# Adafruit_DRV8833.net
KiCad netlist of a schematic drawn in EAGLE
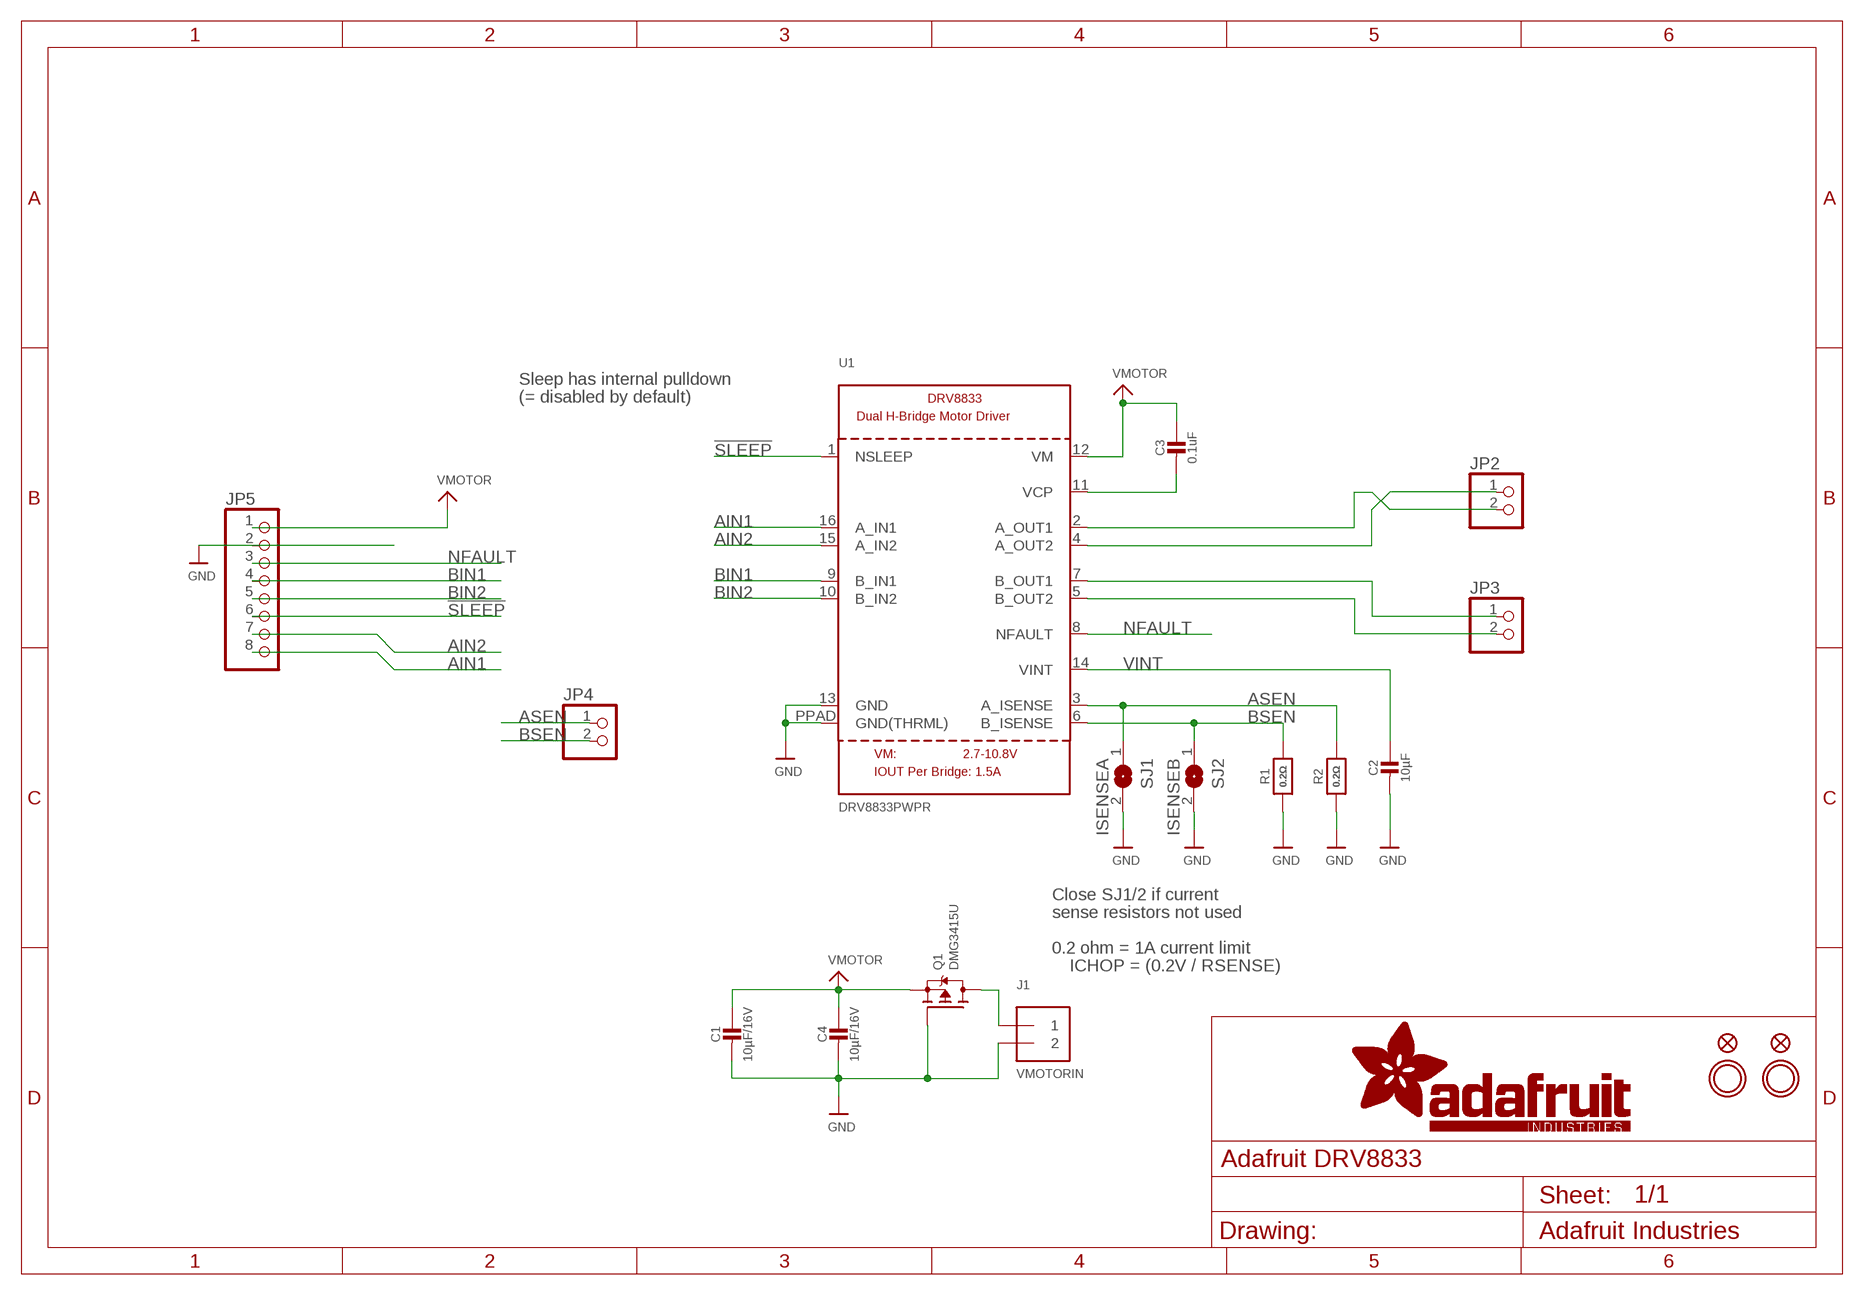
[diagram p0: schematic, sheet 1]

(export (version "E")
  (design (tool "Eeschema 10.0.6"))
  (components
    (comp (ref "C1")
      (value "10µF/16V")
      (footprint "eagle-import:0805-NO")
      (libsource (lib "eagle-import") (part "CAP_CERAMIC0805-NOOUTLINE"))
    )
    (comp (ref "C2")
      (value "10µF")
      (footprint "eagle-import:0805-NO")
      (libsource (lib "eagle-import") (part "CAP_CERAMIC0805-NOOUTLINE"))
    )
    (comp (ref "C3")
      (value "0.1uF")
      (footprint "eagle-import:0805-NO")
      (libsource (lib "eagle-import") (part "CAP_CERAMIC0805-NOOUTLINE"))
    )
    (comp (ref "C4")
      (value "10µF/16V")
      (footprint "eagle-import:0805-NO")
      (libsource (lib "eagle-import") (part "CAP_CERAMIC0805-NOOUTLINE"))
    )
    (comp (ref "FID1")
      (value "FIDUCIAL\"\"")
      (footprint "eagle-import:FIDUCIAL_1MM")
      (libsource (lib "eagle-import") (part "FIDUCIAL{dblquote}{dblquote}"))
    )
    (comp (ref "FID2")
      (value "FIDUCIAL\"\"")
      (footprint "eagle-import:FIDUCIAL_1MM")
      (libsource (lib "eagle-import") (part "FIDUCIAL{dblquote}{dblquote}"))
    )
    (comp (ref "J1")
      (value "VMOTORIN")
      (footprint "eagle-import:TERMBLOCK_1X2-3.5MM")
      (libsource (lib "eagle-import") (part "TERMBLOCK_1X2"))
    )
    (comp (ref "JP2")
      (value "HEADER-1X2ROUND")
      (footprint "eagle-import:1X02_ROUND")
      (libsource (lib "eagle-import") (part "HEADER-1X2ROUND"))
    )
    (comp (ref "JP3")
      (value "HEADER-1X2ROUND")
      (footprint "eagle-import:1X02_ROUND")
      (libsource (lib "eagle-import") (part "HEADER-1X2ROUND"))
    )
    (comp (ref "JP4")
      (value "HEADER-1X2ROUND")
      (footprint "eagle-import:1X02_ROUND")
      (libsource (lib "eagle-import") (part "HEADER-1X2ROUND"))
    )
    (comp (ref "JP5")
      (value "HEADER-1X870MIL")
      (footprint "eagle-import:1X08_ROUND_70")
      (libsource (lib "eagle-import") (part "HEADER-1X870MIL"))
    )
    (comp (ref "Q1")
      (value "DMG3415U")
      (footprint "eagle-import:SOT23-WIDE")
      (libsource (lib "eagle-import") (part "MOSFET-PWIDE"))
    )
    (comp (ref "R1")
      (value "0.2Ω")
      (footprint "eagle-import:_1206")
      (libsource (lib "eagle-import") (part "RESISTOR_1206"))
    )
    (comp (ref "R2")
      (value "0.2Ω")
      (footprint "eagle-import:_1206")
      (libsource (lib "eagle-import") (part "RESISTOR_1206"))
    )
    (comp (ref "SJ1")
      (value "ISENSEA")
      (footprint "eagle-import:SOLDERJUMPER_ARROW_NOPASTE")
      (libsource (lib "eagle-import") (part "SOLDERJUMPER"))
    )
    (comp (ref "SJ2")
      (value "ISENSEB")
      (footprint "eagle-import:SOLDERJUMPER_ARROW_NOPASTE")
      (libsource (lib "eagle-import") (part "SOLDERJUMPER"))
    )
    (comp (ref "U$13")
      (value "MOUNTINGHOLE2.5")
      (footprint "eagle-import:MOUNTINGHOLE_2.5_PLATED")
      (libsource (lib "eagle-import") (part "MOUNTINGHOLE2.5"))
    )
    (comp (ref "U$14")
      (value "MOUNTINGHOLE2.5")
      (footprint "eagle-import:MOUNTINGHOLE_2.5_PLATED")
      (libsource (lib "eagle-import") (part "MOUNTINGHOLE2.5"))
    )
    (comp (ref "U1")
      (value "DRV8833PWPR")
      (footprint "eagle-import:HTSSOP16")
      (libsource (lib "eagle-import") (part "DRV8833"))
    )
  )
  (nets
    (net (code "1") (name "/AIN1") (class "Default")
      (node (ref "JP5") (pin "8") (pinfunction "8_8") (pintype "passive"))
      (node (ref "U1") (pin "16") (pinfunction "A_IN1_16") (pintype "input"))
    )
    (net (code "2") (name "/AIN2") (class "Default")
      (node (ref "JP5") (pin "7") (pinfunction "7_7") (pintype "passive"))
      (node (ref "U1") (pin "15") (pinfunction "A_IN2_15") (pintype "input"))
    )
    (net (code "3") (name "/ASEN") (class "Default")
      (node (ref "JP4") (pin "1") (pinfunction "1_1") (pintype "passive"))
      (node (ref "R2") (pin "2") (pinfunction "2_2") (pintype "passive"))
      (node (ref "SJ1") (pin "1") (pinfunction "1_1") (pintype "passive"))
      (node (ref "U1") (pin "3") (pinfunction "A_ISENSE_3") (pintype "bidirectional"))
    )
    (net (code "4") (name "/BIN1") (class "Default")
      (node (ref "JP5") (pin "4") (pinfunction "4_4") (pintype "passive"))
      (node (ref "U1") (pin "9") (pinfunction "B_IN1_9") (pintype "input"))
    )
    (net (code "5") (name "/BIN2") (class "Default")
      (node (ref "JP5") (pin "5") (pinfunction "5_5") (pintype "passive"))
      (node (ref "U1") (pin "10") (pinfunction "B_IN2_10") (pintype "input"))
    )
    (net (code "6") (name "/BSEN") (class "Default")
      (node (ref "JP4") (pin "2") (pinfunction "2_2") (pintype "passive"))
      (node (ref "R1") (pin "2") (pinfunction "2_2") (pintype "passive"))
      (node (ref "SJ2") (pin "1") (pinfunction "1_1") (pintype "passive"))
      (node (ref "U1") (pin "6") (pinfunction "B_ISENSE_6") (pintype "bidirectional"))
    )
    (net (code "7") (name "/NFAULT") (class "Default")
      (node (ref "JP5") (pin "3") (pinfunction "3_3") (pintype "passive"))
      (node (ref "U1") (pin "8") (pinfunction "NFAULT_8") (pintype "bidirectional"))
    )
    (net (code "8") (name "/VINT") (class "Default")
      (node (ref "C2") (pin "1") (pinfunction "1_1") (pintype "passive"))
      (node (ref "U1") (pin "14") (pinfunction "VINT_14") (pintype "power_in"))
    )
    (net (code "9") (name "/~{SLEEP}") (class "Default")
      (node (ref "JP5") (pin "6") (pinfunction "6_6") (pintype "passive"))
      (node (ref "U1") (pin "1") (pinfunction "NSLEEP_1") (pintype "input"))
    )
    (net (code "10") (name "GND") (class "Default")
      (node (ref "C1") (pin "2") (pinfunction "2_2") (pintype "passive"))
      (node (ref "C2") (pin "2") (pinfunction "2_2") (pintype "passive"))
      (node (ref "C4") (pin "2") (pinfunction "2_2") (pintype "passive"))
      (node (ref "J1") (pin "2") (pinfunction "2_2") (pintype "passive"))
      (node (ref "JP5") (pin "2") (pinfunction "2_2") (pintype "passive"))
      (node (ref "Q1") (pin "1") (pinfunction "G_1") (pintype "passive"))
      (node (ref "R1") (pin "1") (pinfunction "1_1") (pintype "passive"))
      (node (ref "R2") (pin "1") (pinfunction "1_1") (pintype "passive"))
      (node (ref "SJ1") (pin "2") (pinfunction "2_2") (pintype "passive"))
      (node (ref "SJ2") (pin "2") (pinfunction "2_2") (pintype "passive"))
      (node (ref "U1") (pin "13") (pinfunction "GND_13") (pintype "power_in"))
      (node (ref "U1") (pin "PPAD") (pinfunction "GND(THRML)_PPAD") (pintype "power_in"))
    )
    (net (code "11") (name "Net-(Q1-D)") (class "Default")
      (node (ref "J1") (pin "1") (pinfunction "1_1") (pintype "passive"))
      (node (ref "Q1") (pin "3") (pinfunction "D_3") (pintype "passive"))
    )
    (net (code "12") (name "Net-(U1-A_OUT1)") (class "Default")
      (node (ref "JP2") (pin "2") (pinfunction "2_2") (pintype "passive"))
      (node (ref "U1") (pin "2") (pinfunction "A_OUT1_2") (pintype "output"))
    )
    (net (code "13") (name "Net-(U1-A_OUT2)") (class "Default")
      (node (ref "JP2") (pin "1") (pinfunction "1_1") (pintype "passive"))
      (node (ref "U1") (pin "4") (pinfunction "A_OUT2_4") (pintype "output"))
    )
    (net (code "14") (name "Net-(U1-B_OUT1)") (class "Default")
      (node (ref "JP3") (pin "1") (pinfunction "1_1") (pintype "passive"))
      (node (ref "U1") (pin "7") (pinfunction "B_OUT1_7") (pintype "output"))
    )
    (net (code "15") (name "Net-(U1-B_OUT2)") (class "Default")
      (node (ref "JP3") (pin "2") (pinfunction "2_2") (pintype "passive"))
      (node (ref "U1") (pin "5") (pinfunction "B_OUT2_5") (pintype "output"))
    )
    (net (code "16") (name "Net-(U1-VCP)") (class "Default")
      (node (ref "C3") (pin "2") (pinfunction "2_2") (pintype "passive"))
      (node (ref "U1") (pin "11") (pinfunction "VCP_11") (pintype "bidirectional"))
    )
    (net (code "17") (name "VMOTOR") (class "Default")
      (node (ref "C1") (pin "1") (pinfunction "1_1") (pintype "passive"))
      (node (ref "C3") (pin "1") (pinfunction "1_1") (pintype "passive"))
      (node (ref "C4") (pin "1") (pinfunction "1_1") (pintype "passive"))
      (node (ref "JP5") (pin "1") (pinfunction "1_1") (pintype "passive"))
      (node (ref "Q1") (pin "2") (pinfunction "S_2") (pintype "passive"))
      (node (ref "U1") (pin "12") (pinfunction "VM_12") (pintype "power_in"))
    )
  )
)
